# MOSFET.net
KiCad netlist of a schematic drawn in Altium Designer
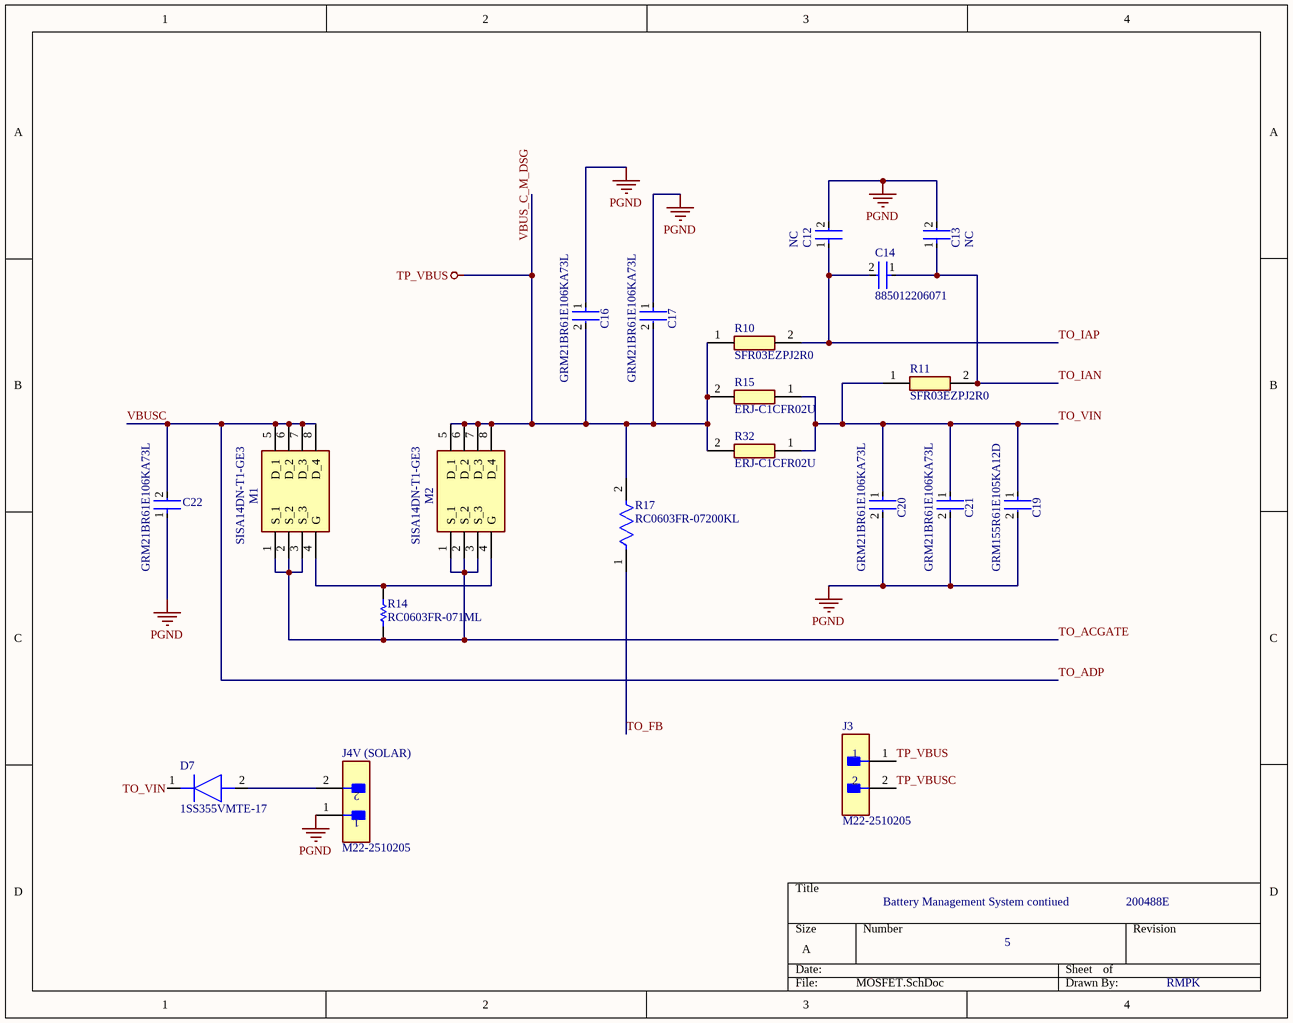
[diagram p0: MOSFET.SchDoc]

(export (version "E")
  (design (tool "Eeschema 10.0.6"))
  (components
    (comp (ref "C12")
      (value "NC")
      (footprint "FP-885012206071-MFG")
      (description "CAP CER 0.1UF 25V X7R 0603")
      (fields (field (name "TOLERANCE") "10%"))
      (libsource (lib "Altium Content Vault") (part "11868f565c42a9108669ba33697ecf6"))
    )
    (comp (ref "C13")
      (value "NC")
      (footprint "FP-885012206071-MFG")
      (description "CAP CER 0.1UF 25V X7R 0603")
      (fields (field (name "TOLERANCE") "10%"))
      (libsource (lib "Altium Content Vault") (part "11868f565c42a9108669ba33697ecf6"))
    )
    (comp (ref "C14")
      (value "885012206071")
      (footprint "FP-885012206071-MFG")
      (description "CAP CER 0.1UF 25V X7R 0603")
      (fields (field (name "TOLERANCE") "10%"))
      (libsource (lib "Altium Content Vault") (part "11868f565c42a9108669ba33697ecf6"))
    )
    (comp (ref "C16")
      (value "GRM21BR61E106KA73L")
      (footprint "FP-GRM21B-0_15-IPC_C")
      (description "Chip Multilayer Ceramic Capacitors for General Purpose, 0805, 10uF, X5R, 15%, 10%, 25V")
      (fields (field (name "VOLTAGE") "25V") (field (name "TOLERANCE") "10%"))
      (libsource (lib "Altium Content Vault") (part "b4654b650e69147ec39a6b967a45e02"))
    )
    (comp (ref "C17")
      (value "GRM21BR61E106KA73L")
      (footprint "FP-GRM21B-0_15-IPC_C")
      (description "Chip Multilayer Ceramic Capacitors for General Purpose, 0805, 10uF, X5R, 15%, 10%, 25V")
      (fields (field (name "VOLTAGE") "25V") (field (name "TOLERANCE") "10%"))
      (libsource (lib "Altium Content Vault") (part "b4654b650e69147ec39a6b967a45e02"))
    )
    (comp (ref "C19")
      (value "GRM155R61E105KA12D")
      (footprint "FP-GRM155-0_05-IPC_B")
      (description "Chip Multilayer Ceramic Capacitors for General Purpose, 0402, 1.0uF, X5R, 15%, 10%, 25V")
      (fields (field (name "VOLTAGE") "25V") (field (name "TOLERANCE") "10%"))
      (libsource (lib "Altium Content Vault") (part "02cd4be3c70576c341d710602a673aa"))
    )
    (comp (ref "C20")
      (value "GRM21BR61E106KA73L")
      (footprint "FP-GRM21B-0_15-IPC_C")
      (description "Chip Multilayer Ceramic Capacitors for General Purpose, 0805, 10uF, X5R, 15%, 10%, 25V")
      (fields (field (name "VOLTAGE") "25V") (field (name "TOLERANCE") "10%"))
      (libsource (lib "Altium Content Vault") (part "b4654b650e69147ec39a6b967a45e02"))
    )
    (comp (ref "C21")
      (value "GRM21BR61E106KA73L")
      (footprint "FP-GRM21B-0_15-IPC_C")
      (description "Chip Multilayer Ceramic Capacitors for General Purpose, 0805, 10uF, X5R, 15%, 10%, 25V")
      (fields (field (name "VOLTAGE") "25V") (field (name "TOLERANCE") "10%"))
      (libsource (lib "Altium Content Vault") (part "b4654b650e69147ec39a6b967a45e02"))
    )
    (comp (ref "C22")
      (value "GRM21BR61E106KA73L")
      (footprint "FP-GRM21B-0_15-IPC_C")
      (description "Chip Multilayer Ceramic Capacitors for General Purpose, 0805, 10uF, X5R, 15%, 10%, 25V")
      (fields (field (name "VOLTAGE") "25V") (field (name "TOLERANCE") "10%"))
      (libsource (lib "Altium Content Vault") (part "b4654b650e69147ec39a6b967a45e02"))
    )
    (comp (ref "D7")
      (value "1SS355VMTE-17")
      (footprint "SamacSys:UDZVTE1722B")
      (description "Diode")
      (fields (field (name "MOUSER PART NUMBER") "755-1SS355VMTE-17"))
      (libsource (lib "*") (part "1SS355VMTE-17"))
    )
    (comp (ref "J3")
      (value "M22-2510205")
      (footprint "FP-M22-2510205-MFG")
      (description "CONN HEADER VERT 2POS 2MM")
      (fields
        (field (name "MANUFACTURER") "Harwin")
        (field (name "OCTOPART") "https://octopart.com/m22-2510205-harwin-2538221")
      )
      (libsource (lib "Altium Content Vault") (part "3bc925449376181038e59eaffc5286c"))
    )
    (comp (ref "J4V (SOLAR)")
      (value "M22-2510205")
      (footprint "FP-M22-2510205-MFG")
      (description "CONN HEADER VERT 2POS 2MM")
      (fields
        (field (name "MANUFACTURER") "Harwin")
        (field (name "OCTOPART") "https://octopart.com/m22-2510205-harwin-2538221")
      )
      (libsource (lib "") (part "3bc925449376181038e59eaffc5286c_1"))
    )
    (comp (ref "M1")
      (value "SISA14DN-T1-GE3")
      (footprint "SamacSys:SQ7414AENT1GE3")
      (description "MOSFET (N-Channel)")
      (fields (field (name "MOUSER PART NUMBER") "78-SISA14DN-T1-GE3"))
      (libsource (lib "*") (part "SISA14DN-T1-GE3"))
    )
    (comp (ref "M2")
      (value "SISA14DN-T1-GE3")
      (footprint "SamacSys:SQ7414AENT1GE3")
      (description "MOSFET (N-Channel)")
      (fields (field (name "MOUSER PART NUMBER") "78-SISA14DN-T1-GE3"))
      (libsource (lib "*") (part "SISA14DN-T1-GE3"))
    )
    (comp (ref "R10")
      (value "SFR03EZPJ2R0")
      (footprint "SamacSys:RESC1608X55N")
      (description "Resistor")
      (libsource (lib "*") (part "SFR03EZPJ2R0"))
    )
    (comp (ref "R11")
      (value "SFR03EZPJ2R0")
      (footprint "SamacSys:RESC1608X55N")
      (description "Resistor")
      (libsource (lib "*") (part "SFR03EZPJ2R0"))
    )
    (comp (ref "R14")
      (value "RC0603FR-071ML")
      (footprint "RESC1608X55X25LL10T15")
      (description "Chip Resistor, 1 MOhm, +/- 1%, 100 mW, -55 to 155 degC, 0603 (1608 Metric), RoHS, Tape and Reel")
      (fields (field (name "TOLERANCE") "20%"))
      (libsource (lib "Altium Content Vault") (part "RES-2"))
    )
    (comp (ref "R15")
      (value "ERJ-C1CFR02U")
      (footprint "SamacSys:ERJC1")
      (description "Resistor")
      (fields (field (name "MOUSER PART NUMBER") "667-ERJ-C1CFR02U"))
      (libsource (lib "*") (part "ERJ-C1CFR02U"))
    )
    (comp (ref "R17")
      (value "RC0603FR-07200KL")
      (footprint "FP-RC0603-0_55-IPC_B")
      (description "RES SMD 200K OHM 1% 1/10W 0603")
      (fields (field (name "TOLERANCE") "1%"))
      (libsource (lib "Altium Content Vault") (part "1029c3af85768c4190bb7ad29bc67b5"))
    )
    (comp (ref "R32")
      (value "ERJ-C1CFR02U")
      (footprint "SamacSys:ERJC1")
      (description "Resistor")
      (fields (field (name "MOUSER PART NUMBER") "667-ERJ-C1CFR02U"))
      (libsource (lib "*") (part "ERJ-C1CFR02U"))
    )
  )
  (nets
    (net (code "1") (name "/TO_ACGATE") (class "Default")
      (node (ref "M1") (pin "1") (pinfunction "S_1_1") (pintype "passive"))
      (node (ref "M1") (pin "2") (pinfunction "S_2_2") (pintype "passive"))
      (node (ref "M1") (pin "3") (pinfunction "S_3_3") (pintype "passive"))
      (node (ref "M2") (pin "1") (pinfunction "S_1_1") (pintype "passive"))
      (node (ref "M2") (pin "2") (pinfunction "S_2_2") (pintype "passive"))
      (node (ref "M2") (pin "3") (pinfunction "S_3_3") (pintype "passive"))
      (node (ref "R14") (pin "1") (pinfunction "1_1") (pintype "passive"))
    )
    (net (code "2") (name "/TO_ADP") (class "Default")
      (node (ref "C22") (pin "2") (pinfunction "2_2") (pintype "passive"))
      (node (ref "M1") (pin "5") (pinfunction "D_1_5") (pintype "passive"))
      (node (ref "M1") (pin "6") (pinfunction "D_2_6") (pintype "passive"))
      (node (ref "M1") (pin "7") (pinfunction "D_3_7") (pintype "passive"))
      (node (ref "M1") (pin "8") (pinfunction "D_4_8") (pintype "passive"))
    )
    (net (code "3") (name "/TO_FB") (class "Default")
      (node (ref "R17") (pin "1") (pinfunction "1_1") (pintype "passive"))
    )
    (net (code "4") (name "/TO_IAN") (class "Default")
      (node (ref "C13") (pin "1") (pinfunction "1_1") (pintype "passive"))
      (node (ref "C14") (pin "1") (pinfunction "1_1") (pintype "passive"))
      (node (ref "R11") (pin "2") (pinfunction "2_2") (pintype "passive"))
    )
    (net (code "5") (name "/TO_IAP") (class "Default")
      (node (ref "C12") (pin "1") (pinfunction "1_1") (pintype "passive"))
      (node (ref "C14") (pin "2") (pinfunction "2_2") (pintype "passive"))
      (node (ref "R10") (pin "2") (pinfunction "2_2") (pintype "passive"))
    )
    (net (code "6") (name "/TO_VIN") (class "Default")
      (node (ref "C19") (pin "1") (pinfunction "1_1") (pintype "passive"))
      (node (ref "C20") (pin "1") (pinfunction "1_1") (pintype "passive"))
      (node (ref "C21") (pin "1") (pinfunction "1_1") (pintype "passive"))
      (node (ref "D7") (pin "1") (pinfunction "K_1") (pintype "passive"))
      (node (ref "R11") (pin "1") (pinfunction "1_1") (pintype "passive"))
      (node (ref "R15") (pin "1") (pinfunction "1_1") (pintype "passive"))
      (node (ref "R32") (pin "1") (pinfunction "1_1") (pintype "passive"))
    )
    (net (code "7") (name "/TP_VBUSC") (class "Default")
      (node (ref "J3") (pin "2") (pinfunction "2_2") (pintype "passive"))
    )
    (net (code "8") (name "Net-(D7-A)") (class "Default")
      (node (ref "D7") (pin "2") (pinfunction "A_2") (pintype "passive"))
      (node (ref "J4V (SOLAR)") (pin "2") (pinfunction "2_2") (pintype "passive"))
    )
    (net (code "9") (name "Net-(M1-G)") (class "Default")
      (node (ref "M1") (pin "4") (pinfunction "G_4") (pintype "passive"))
      (node (ref "M2") (pin "4") (pinfunction "G_4") (pintype "passive"))
      (node (ref "R14") (pin "2") (pinfunction "2_2") (pintype "passive"))
    )
    (net (code "10") (name "PGND") (class "Default")
      (node (ref "C12") (pin "2") (pinfunction "2_2") (pintype "passive"))
      (node (ref "C13") (pin "2") (pinfunction "2_2") (pintype "passive"))
      (node (ref "C16") (pin "1") (pinfunction "1_1") (pintype "passive"))
      (node (ref "C17") (pin "1") (pinfunction "1_1") (pintype "passive"))
      (node (ref "C19") (pin "2") (pinfunction "2_2") (pintype "passive"))
      (node (ref "C20") (pin "2") (pinfunction "2_2") (pintype "passive"))
      (node (ref "C21") (pin "2") (pinfunction "2_2") (pintype "passive"))
      (node (ref "C22") (pin "1") (pinfunction "1_1") (pintype "passive"))
      (node (ref "J4V (SOLAR)") (pin "1") (pinfunction "1_1") (pintype "passive"))
    )
    (net (code "11") (name "TP_VBUS") (class "Default")
      (node (ref "C16") (pin "2") (pinfunction "2_2") (pintype "passive"))
      (node (ref "C17") (pin "2") (pinfunction "2_2") (pintype "passive"))
      (node (ref "J3") (pin "1") (pinfunction "1_1") (pintype "passive"))
      (node (ref "M2") (pin "5") (pinfunction "D_1_5") (pintype "passive"))
      (node (ref "M2") (pin "6") (pinfunction "D_2_6") (pintype "passive"))
      (node (ref "M2") (pin "7") (pinfunction "D_3_7") (pintype "passive"))
      (node (ref "M2") (pin "8") (pinfunction "D_4_8") (pintype "passive"))
      (node (ref "R10") (pin "1") (pinfunction "1_1") (pintype "passive"))
      (node (ref "R15") (pin "2") (pinfunction "2_2") (pintype "passive"))
      (node (ref "R17") (pin "2") (pinfunction "2_2") (pintype "passive"))
      (node (ref "R32") (pin "2") (pinfunction "2_2") (pintype "passive"))
    )
  )
)
